# rev2.net
KiCad netlist of a schematic drawn in EAGLE
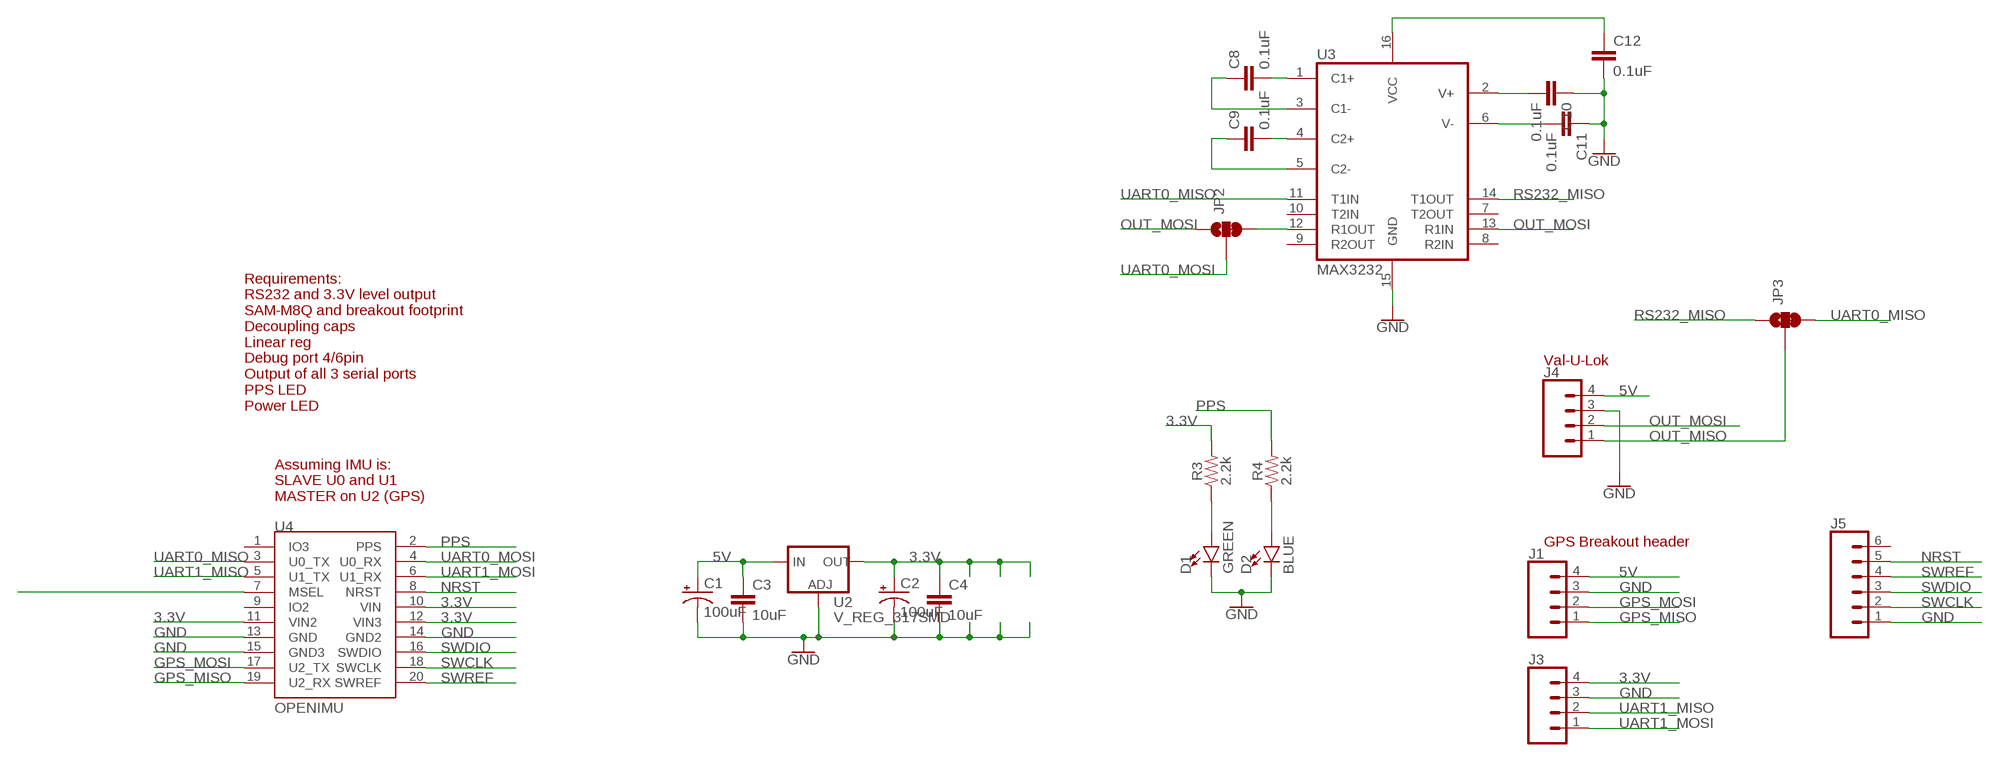
[diagram p0: schematic, sheet 1]

(export (version "E")
  (design (tool "Eeschema 10.0.6"))
  (components
    (comp (ref "C1")
      (value "100uF")
      (footprint "eagle-import:EIA3528")
      (libsource (lib "eagle-import") (part "47UF-POLAR-EIA3528-10V-10%"))
    )
    (comp (ref "C2")
      (value "100uF")
      (footprint "eagle-import:EIA3528")
      (libsource (lib "eagle-import") (part "47UF-POLAR-EIA3528-10V-10%"))
    )
    (comp (ref "C3")
      (value "10uF")
      (footprint "eagle-import:0805")
      (libsource (lib "eagle-import") (part "10UF-0805-10V-10%"))
    )
    (comp (ref "C4")
      (value "10uF")
      (footprint "eagle-import:0805")
      (libsource (lib "eagle-import") (part "10UF-0805-10V-10%"))
    )
    (comp (ref "C8")
      (value "0.1uF")
      (footprint "eagle-import:0603")
      (libsource (lib "eagle-import") (part "0.1UF-0603-25V-5%"))
    )
    (comp (ref "C9")
      (value "0.1uF")
      (footprint "eagle-import:0603")
      (libsource (lib "eagle-import") (part "0.1UF-0603-25V-5%"))
    )
    (comp (ref "C10")
      (value "0.1uF")
      (footprint "eagle-import:0603")
      (libsource (lib "eagle-import") (part "0.1UF-0603-25V-5%"))
    )
    (comp (ref "C11")
      (value "0.1uF")
      (footprint "eagle-import:0603")
      (libsource (lib "eagle-import") (part "0.1UF-0603-25V-5%"))
    )
    (comp (ref "C12")
      (value "0.1uF")
      (footprint "eagle-import:0603")
      (libsource (lib "eagle-import") (part "0.1UF-0603-25V-5%"))
    )
    (comp (ref "D1")
      (value "GREEN")
      (footprint "eagle-import:LED-0603")
      (libsource (lib "eagle-import") (part "LED-GREEN0603"))
    )
    (comp (ref "D2")
      (value "BLUE")
      (footprint "eagle-import:LED-0603")
      (libsource (lib "eagle-import") (part "LED-BLUE0603"))
    )
    (comp (ref "J1")
      (value "CONN_04")
      (footprint "eagle-import:1X04")
      (libsource (lib "eagle-import") (part "CONN_04"))
    )
    (comp (ref "J3")
      (value "CONN_04")
      (footprint "eagle-import:1X04")
      (libsource (lib "eagle-import") (part "CONN_04"))
    )
    (comp (ref "J4")
      (value "CONN_04POLAR")
      (footprint "eagle-import:MOLEX-1X4")
      (libsource (lib "eagle-import") (part "CONN_04POLAR"))
    )
    (comp (ref "J5")
      (value "CONN_06POLAR")
      (footprint "eagle-import:MOLEX-1X6")
      (libsource (lib "eagle-import") (part "CONN_06POLAR"))
    )
    (comp (ref "JP2")
      (value "JUMPER-SMT_3_1-NC_TRACE_SILK")
      (footprint "eagle-import:SMT-JUMPER_3_1-NC_TRACE_SILK")
      (libsource (lib "eagle-import") (part "JUMPER-SMT_3_1-NC_TRACE_SILK"))
    )
    (comp (ref "JP3")
      (value "JUMPER-SMT_3_1-NC_TRACE_SILK")
      (footprint "eagle-import:SMT-JUMPER_3_1-NC_TRACE_SILK")
      (libsource (lib "eagle-import") (part "JUMPER-SMT_3_1-NC_TRACE_SILK"))
    )
    (comp (ref "R3")
      (value "2.2k")
      (footprint "eagle-import:0603")
      (libsource (lib "eagle-import") (part "2.2KOHM-0603-1/10W-1%"))
    )
    (comp (ref "R4")
      (value "2.2k")
      (footprint "eagle-import:0603")
      (libsource (lib "eagle-import") (part "2.2KOHM-0603-1/10W-1%"))
    )
    (comp (ref "U2")
      (value "V_REG_317SMD")
      (footprint "eagle-import:SOT223")
      (libsource (lib "eagle-import") (part "V_REG_317SMD"))
    )
    (comp (ref "U3")
      (value "MAX3232")
      (footprint "eagle-import:TSSOP16")
      (libsource (lib "eagle-import") (part "MAX2323TSSOP"))
    )
    (comp (ref "U4")
      (value "OPENIMU")
      (footprint "eagle-import:OPENIMU300ZA")
      (libsource (lib "eagle-import") (part "OPENIMU"))
    )
  )
  (nets
    (net (code "1") (name "/3.3V") (class "Default")
      (node (ref "C2") (pin "A") (pinfunction "+_A") (pintype "passive"))
      (node (ref "C4") (pin "1") (pinfunction "1_1") (pintype "passive"))
      (node (ref "J3") (pin "4") (pinfunction "4_4") (pintype "passive"))
      (node (ref "R3") (pin "2") (pinfunction "2_2") (pintype "passive"))
      (node (ref "U2") (pin "2") (pinfunction "OUT_2") (pintype "output"))
      (node (ref "U4") (pin "10") (pinfunction "VIN_10") (pintype "bidirectional"))
      (node (ref "U4") (pin "11") (pinfunction "VIN2_11") (pintype "bidirectional"))
      (node (ref "U4") (pin "12") (pinfunction "VIN3_12") (pintype "bidirectional"))
    )
    (net (code "2") (name "/5V") (class "Default")
      (node (ref "C1") (pin "A") (pinfunction "+_A") (pintype "passive"))
      (node (ref "C3") (pin "1") (pinfunction "1_1") (pintype "passive"))
      (node (ref "J1") (pin "4") (pinfunction "4_4") (pintype "passive"))
      (node (ref "J4") (pin "4") (pinfunction "4_4") (pintype "passive"))
      (node (ref "U2") (pin "3") (pinfunction "IN_3") (pintype "input"))
    )
    (net (code "3") (name "/GPS_MISO") (class "Default")
      (node (ref "J1") (pin "1") (pinfunction "1_1") (pintype "passive"))
      (node (ref "U4") (pin "19") (pinfunction "U2_RX_19") (pintype "bidirectional"))
    )
    (net (code "4") (name "/GPS_MOSI") (class "Default")
      (node (ref "J1") (pin "2") (pinfunction "2_2") (pintype "passive"))
      (node (ref "U4") (pin "17") (pinfunction "U2_TX_17") (pintype "bidirectional"))
    )
    (net (code "5") (name "/NRST") (class "Default")
      (node (ref "J5") (pin "5") (pinfunction "5_5") (pintype "passive"))
      (node (ref "U4") (pin "8") (pinfunction "NRST_8") (pintype "bidirectional"))
    )
    (net (code "6") (name "/OUT_MISO") (class "Default")
      (node (ref "J4") (pin "1") (pinfunction "1_1") (pintype "passive"))
      (node (ref "JP3") (pin "2") (pinfunction "2_2") (pintype "passive"))
    )
    (net (code "7") (name "/OUT_MOSI") (class "Default")
      (node (ref "J4") (pin "2") (pinfunction "2_2") (pintype "passive"))
      (node (ref "JP2") (pin "1") (pinfunction "1_1") (pintype "passive"))
      (node (ref "U3") (pin "13") (pinfunction "R1IN_13") (pintype "input"))
    )
    (net (code "8") (name "/PPS") (class "Default")
      (node (ref "R4") (pin "2") (pinfunction "2_2") (pintype "passive"))
      (node (ref "U4") (pin "2") (pinfunction "PPS_2") (pintype "bidirectional"))
    )
    (net (code "9") (name "/RS232_MISO") (class "Default")
      (node (ref "JP3") (pin "1") (pinfunction "1_1") (pintype "passive"))
      (node (ref "U3") (pin "14") (pinfunction "T1OUT_14") (pintype "output"))
    )
    (net (code "10") (name "/SWCLK") (class "Default")
      (node (ref "J5") (pin "2") (pinfunction "2_2") (pintype "passive"))
      (node (ref "U4") (pin "18") (pinfunction "SWCLK_18") (pintype "bidirectional"))
    )
    (net (code "11") (name "/SWDIO") (class "Default")
      (node (ref "J5") (pin "3") (pinfunction "3_3") (pintype "passive"))
      (node (ref "U4") (pin "16") (pinfunction "SWDIO_16") (pintype "bidirectional"))
    )
    (net (code "12") (name "/SWREF") (class "Default")
      (node (ref "J5") (pin "4") (pinfunction "4_4") (pintype "passive"))
      (node (ref "U4") (pin "20") (pinfunction "SWREF_20") (pintype "bidirectional"))
    )
    (net (code "13") (name "/UART0_MISO") (class "Default")
      (node (ref "JP3") (pin "3") (pinfunction "3_3") (pintype "passive"))
      (node (ref "U3") (pin "11") (pinfunction "T1IN_11") (pintype "input"))
      (node (ref "U4") (pin "3") (pinfunction "U0_TX_3") (pintype "bidirectional"))
    )
    (net (code "14") (name "/UART0_MOSI") (class "Default")
      (node (ref "JP2") (pin "2") (pinfunction "2_2") (pintype "passive"))
      (node (ref "U4") (pin "4") (pinfunction "U0_RX_4") (pintype "bidirectional"))
    )
    (net (code "15") (name "/UART1_MISO") (class "Default")
      (node (ref "J3") (pin "2") (pinfunction "2_2") (pintype "passive"))
      (node (ref "U4") (pin "5") (pinfunction "U1_TX_5") (pintype "bidirectional"))
    )
    (net (code "16") (name "/UART1_MOSI") (class "Default")
      (node (ref "J3") (pin "1") (pinfunction "1_1") (pintype "passive"))
      (node (ref "U4") (pin "6") (pinfunction "U1_RX_6") (pintype "bidirectional"))
    )
    (net (code "17") (name "GND") (class "Default")
      (node (ref "C1") (pin "C") (pinfunction "-_C") (pintype "passive"))
      (node (ref "C10") (pin "1") (pinfunction "1_1") (pintype "passive"))
      (node (ref "C11") (pin "1") (pinfunction "1_1") (pintype "passive"))
      (node (ref "C12") (pin "2") (pinfunction "2_2") (pintype "passive"))
      (node (ref "C2") (pin "C") (pinfunction "-_C") (pintype "passive"))
      (node (ref "C3") (pin "2") (pinfunction "2_2") (pintype "passive"))
      (node (ref "C4") (pin "2") (pinfunction "2_2") (pintype "passive"))
      (node (ref "D1") (pin "C") (pinfunction "C_C") (pintype "passive"))
      (node (ref "D2") (pin "C") (pinfunction "C_C") (pintype "passive"))
      (node (ref "J1") (pin "3") (pinfunction "3_3") (pintype "passive"))
      (node (ref "J3") (pin "3") (pinfunction "3_3") (pintype "passive"))
      (node (ref "J4") (pin "3") (pinfunction "3_3") (pintype "passive"))
      (node (ref "J5") (pin "1") (pinfunction "1_1") (pintype "passive"))
      (node (ref "U2") (pin "1") (pinfunction "ADJ_1") (pintype "input"))
      (node (ref "U3") (pin "15") (pinfunction "GND_15") (pintype "bidirectional"))
      (node (ref "U4") (pin "13") (pinfunction "GND_13") (pintype "bidirectional"))
      (node (ref "U4") (pin "14") (pinfunction "GND2_14") (pintype "bidirectional"))
      (node (ref "U4") (pin "15") (pinfunction "GND3_15") (pintype "bidirectional"))
    )
    (net (code "18") (name "Net-(D1-PadA)") (class "Default")
      (node (ref "D1") (pin "A") (pinfunction "A_A") (pintype "passive"))
      (node (ref "R3") (pin "1") (pinfunction "1_1") (pintype "passive"))
    )
    (net (code "19") (name "Net-(D2-PadA)") (class "Default")
      (node (ref "D2") (pin "A") (pinfunction "A_A") (pintype "passive"))
      (node (ref "R4") (pin "1") (pinfunction "1_1") (pintype "passive"))
    )
    (net (code "20") (name "Net-(U3-C1+)") (class "Default")
      (node (ref "C8") (pin "2") (pinfunction "2_2") (pintype "passive"))
      (node (ref "U3") (pin "1") (pinfunction "C1+_1") (pintype "bidirectional"))
    )
    (net (code "21") (name "Net-(U3-C1-)") (class "Default")
      (node (ref "C8") (pin "1") (pinfunction "1_1") (pintype "passive"))
      (node (ref "U3") (pin "3") (pinfunction "C1-_3") (pintype "bidirectional"))
    )
    (net (code "22") (name "Net-(U3-C2+)") (class "Default")
      (node (ref "C9") (pin "2") (pinfunction "2_2") (pintype "passive"))
      (node (ref "U3") (pin "4") (pinfunction "C2+_4") (pintype "bidirectional"))
    )
    (net (code "23") (name "Net-(U3-C2-)") (class "Default")
      (node (ref "C9") (pin "1") (pinfunction "1_1") (pintype "passive"))
      (node (ref "U3") (pin "5") (pinfunction "C2-_5") (pintype "bidirectional"))
    )
    (net (code "24") (name "Net-(U3-R1OUT)") (class "Default")
      (node (ref "JP2") (pin "3") (pinfunction "3_3") (pintype "passive"))
      (node (ref "U3") (pin "12") (pinfunction "R1OUT_12") (pintype "output"))
    )
    (net (code "25") (name "Net-(U3-V+)") (class "Default")
      (node (ref "C10") (pin "2") (pinfunction "2_2") (pintype "passive"))
      (node (ref "U3") (pin "2") (pinfunction "V+_2") (pintype "bidirectional"))
    )
    (net (code "26") (name "Net-(U3-V-)") (class "Default")
      (node (ref "C11") (pin "2") (pinfunction "2_2") (pintype "passive"))
      (node (ref "U3") (pin "6") (pinfunction "V-_6") (pintype "bidirectional"))
    )
    (net (code "27") (name "Net-(U3-VCC)") (class "Default")
      (node (ref "C12") (pin "1") (pinfunction "1_1") (pintype "passive"))
      (node (ref "U3") (pin "16") (pinfunction "VCC_16") (pintype "bidirectional"))
    )
    (net (code "28") (name "unconnected-(J5-Pad6)") (class "Default")
      (node (ref "J5") (pin "6") (pinfunction "6_6") (pintype "passive"))
    )
    (net (code "29") (name "unconnected-(U3-R2IN-Pad8)") (class "Default")
      (node (ref "U3") (pin "8") (pinfunction "R2IN_8") (pintype "input"))
    )
    (net (code "30") (name "unconnected-(U3-R2OUT-Pad9)") (class "Default")
      (node (ref "U3") (pin "9") (pinfunction "R2OUT_9") (pintype "output"))
    )
    (net (code "31") (name "unconnected-(U3-T2IN-Pad10)") (class "Default")
      (node (ref "U3") (pin "10") (pinfunction "T2IN_10") (pintype "input"))
    )
    (net (code "32") (name "unconnected-(U3-T2OUT-Pad7)") (class "Default")
      (node (ref "U3") (pin "7") (pinfunction "T2OUT_7") (pintype "output"))
    )
    (net (code "33") (name "unconnected-(U4-IO2-Pad9)") (class "Default")
      (node (ref "U4") (pin "9") (pinfunction "IO2_9") (pintype "bidirectional"))
    )
    (net (code "34") (name "unconnected-(U4-IO3-Pad1)") (class "Default")
      (node (ref "U4") (pin "1") (pinfunction "IO3_1") (pintype "bidirectional"))
    )
    (net (code "35") (name "unconnected-(U4-MSEL-Pad7)") (class "Default")
      (node (ref "U4") (pin "7") (pinfunction "MSEL_7") (pintype "bidirectional"))
    )
  )
)
